# p3.net
KiCad netlist of a schematic drawn in EAGLE
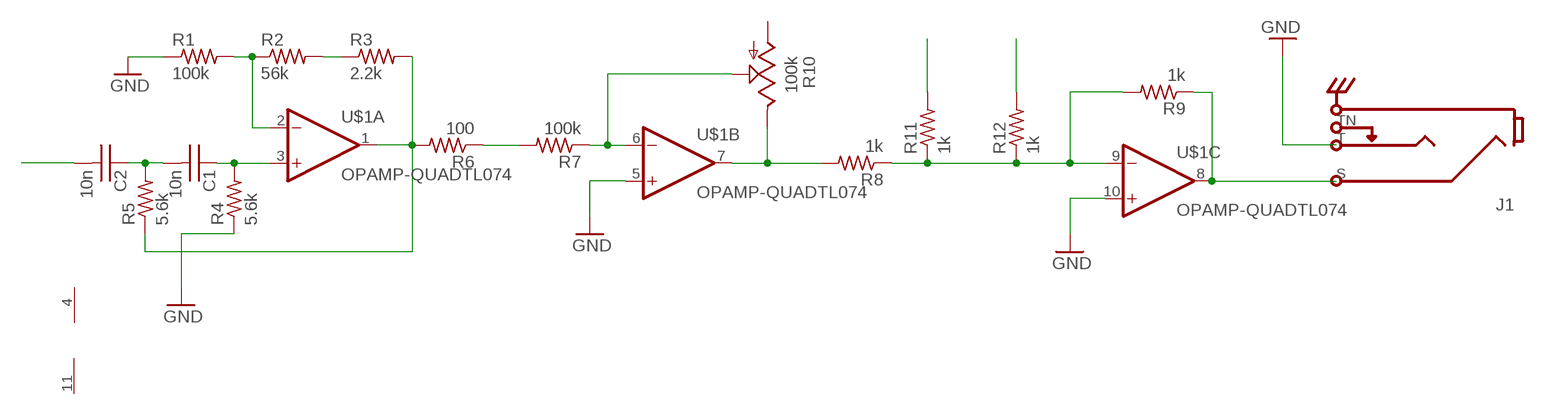
[diagram p0: schematic, sheet 1]

(export (version "E")
  (design (tool "Eeschema 10.0.6"))
  (components
    (comp (ref "C1")
      (value "10n")
      (footprint "eagle-import:BOX-2.5MM-7.2MM")
      (libsource (lib "eagle-import") (part "CAPACITOR"))
    )
    (comp (ref "C2")
      (value "10n")
      (footprint "eagle-import:BOX-2.5MM-7.2MM")
      (libsource (lib "eagle-import") (part "CAPACITOR"))
    )
    (comp (ref "J1")
      (value "MONOSW1GND")
      (footprint "eagle-import:NEUTRIK-NRJ4HM-1")
      (libsource (lib "eagle-import") (part "MONOSW1GND"))
    )
    (comp (ref "R1")
      (value "100k")
      (footprint "eagle-import:0.25W-0.4IN-METALFILM")
      (libsource (lib "eagle-import") (part "RESISTOR0.25W-0.4IN-METALFILM"))
    )
    (comp (ref "R2")
      (value "56k")
      (footprint "eagle-import:0.25W-0.4IN-METALFILM")
      (libsource (lib "eagle-import") (part "RESISTOR0.25W-0.4IN-METALFILM"))
    )
    (comp (ref "R3")
      (value "2.2k")
      (footprint "eagle-import:0.25W-0.4IN-METALFILM")
      (libsource (lib "eagle-import") (part "RESISTOR0.25W-0.4IN-METALFILM"))
    )
    (comp (ref "R4")
      (value "5.6k")
      (footprint "eagle-import:0.25W-0.4IN-METALFILM")
      (libsource (lib "eagle-import") (part "RESISTOR0.25W-0.4IN-METALFILM"))
    )
    (comp (ref "R5")
      (value "5.6k")
      (footprint "eagle-import:0.25W-0.4IN-METALFILM")
      (libsource (lib "eagle-import") (part "RESISTOR0.25W-0.4IN-METALFILM"))
    )
    (comp (ref "R6")
      (value "100")
      (footprint "eagle-import:0.25W-0.4IN-METALFILM")
      (libsource (lib "eagle-import") (part "RESISTOR0.25W-0.4IN-METALFILM"))
    )
    (comp (ref "R7")
      (value "100k")
      (footprint "eagle-import:0.25W-0.4IN-METALFILM")
      (libsource (lib "eagle-import") (part "RESISTOR0.25W-0.4IN-METALFILM"))
    )
    (comp (ref "R8")
      (value "1k")
      (footprint "eagle-import:0.25W-0.4IN-METALFILM")
      (libsource (lib "eagle-import") (part "RESISTOR0.25W-0.4IN-METALFILM"))
    )
    (comp (ref "R9")
      (value "1k")
      (footprint "eagle-import:0.25W-0.4IN-METALFILM")
      (libsource (lib "eagle-import") (part "RESISTOR0.25W-0.4IN-METALFILM"))
    )
    (comp (ref "R10")
      (value "100k")
      (footprint "eagle-import:POT-SIDE-16MM-BITECH-P160KN")
      (libsource (lib "eagle-import") (part "POTENTIOMETERHORIZONTAL"))
    )
    (comp (ref "R11")
      (value "1k")
      (footprint "eagle-import:0.25W-0.4IN")
      (libsource (lib "eagle-import") (part "RESISTOR0.25W-0.4IN"))
    )
    (comp (ref "R12")
      (value "1k")
      (footprint "eagle-import:0.25W-0.4IN")
      (libsource (lib "eagle-import") (part "RESISTOR0.25W-0.4IN"))
    )
    (comp (ref "U$1")
      (value "OPAMP-QUADTL074")
      (footprint "eagle-import:DIP14")
      (libsource (lib "eagle-import") (part "OPAMP-QUADTL074"))
    )
  )
  (nets
    (net (code "1") (name "/VCC") (class "Default")
      (node (ref "U$1") (pin "4") (pinfunction "VCC_4") (pintype "power_in"))
    )
    (net (code "2") (name "/VEE") (class "Default")
      (node (ref "U$1") (pin "11") (pinfunction "VEE_11") (pintype "power_in"))
    )
    (net (code "3") (name "0") (class "Default")
      (node (ref "J1") (pin "T") (pinfunction "T_T") (pintype "passive"))
      (node (ref "R1") (pin "1") (pinfunction "1_1") (pintype "passive"))
      (node (ref "R4") (pin "1") (pinfunction "1_1") (pintype "passive"))
      (node (ref "U$1") (pin "10") (pinfunction "IN+_10") (pintype "input"))
      (node (ref "U$1") (pin "5") (pinfunction "IN+_5") (pintype "input"))
    )
    (net (code "4") (name "Net-(C1-1)") (class "Default")
      (node (ref "C1") (pin "P$1") (pinfunction "1_P$1") (pintype "passive"))
      (node (ref "R4") (pin "2") (pinfunction "2_2") (pintype "passive"))
      (node (ref "U$1") (pin "3") (pinfunction "IN+_3") (pintype "input"))
    )
    (net (code "5") (name "Net-(C1-2)") (class "Default")
      (node (ref "C1") (pin "P$2") (pinfunction "2_P$2") (pintype "passive"))
      (node (ref "C2") (pin "P$1") (pinfunction "1_P$1") (pintype "passive"))
      (node (ref "R5") (pin "2") (pinfunction "2_2") (pintype "passive"))
    )
    (net (code "6") (name "Net-(R2-Pad2)") (class "Default")
      (node (ref "R2") (pin "2") (pinfunction "2_2") (pintype "passive"))
      (node (ref "R3") (pin "1") (pinfunction "1_1") (pintype "passive"))
    )
    (net (code "7") (name "Net-(R6-Pad1)") (class "Default")
      (node (ref "R6") (pin "1") (pinfunction "1_1") (pintype "passive"))
      (node (ref "R7") (pin "2") (pinfunction "2_2") (pintype "passive"))
    )
    (net (code "8") (name "Net-(R10-2)") (class "Default")
      (node (ref "R10") (pin "P$2") (pinfunction "2_P$2") (pintype "passive"))
      (node (ref "R7") (pin "1") (pinfunction "1_1") (pintype "passive"))
      (node (ref "U$1") (pin "6") (pinfunction "IN-_6") (pintype "input"))
    )
    (net (code "9") (name "Net-(R10-3)") (class "Default")
      (node (ref "R10") (pin "P$3") (pinfunction "3_P$3") (pintype "passive"))
      (node (ref "R8") (pin "2") (pinfunction "2_2") (pintype "passive"))
      (node (ref "U$1") (pin "7") (pinfunction "OUT_7") (pintype "output"))
    )
    (net (code "10") (name "Net-(U$1A-IN-)") (class "Default")
      (node (ref "R1") (pin "2") (pinfunction "2_2") (pintype "passive"))
      (node (ref "R2") (pin "1") (pinfunction "1_1") (pintype "passive"))
      (node (ref "U$1") (pin "2") (pinfunction "IN-_2") (pintype "input"))
    )
    (net (code "11") (name "Net-(U$1A-OUT)") (class "Default")
      (node (ref "R3") (pin "2") (pinfunction "2_2") (pintype "passive"))
      (node (ref "R5") (pin "1") (pinfunction "1_1") (pintype "passive"))
      (node (ref "R6") (pin "2") (pinfunction "2_2") (pintype "passive"))
      (node (ref "U$1") (pin "1") (pinfunction "OUT_1") (pintype "output"))
    )
    (net (code "12") (name "Net-(U$1C-IN-)") (class "Default")
      (node (ref "R11") (pin "1") (pinfunction "1_1") (pintype "passive"))
      (node (ref "R12") (pin "1") (pinfunction "1_1") (pintype "passive"))
      (node (ref "R8") (pin "1") (pinfunction "1_1") (pintype "passive"))
      (node (ref "R9") (pin "2") (pinfunction "2_2") (pintype "passive"))
      (node (ref "U$1") (pin "9") (pinfunction "IN-_9") (pintype "input"))
    )
    (net (code "13") (name "Net-(U$1C-OUT)") (class "Default")
      (node (ref "J1") (pin "S") (pinfunction "S_S") (pintype "passive"))
      (node (ref "R9") (pin "1") (pinfunction "1_1") (pintype "passive"))
      (node (ref "U$1") (pin "8") (pinfunction "OUT_8") (pintype "output"))
    )
    (net (code "14") (name "unconnected-(C2-2-PadP$2)") (class "Default")
      (node (ref "C2") (pin "P$2") (pinfunction "2_P$2") (pintype "passive"))
    )
    (net (code "15") (name "unconnected-(J1-PadTN)") (class "Default")
      (node (ref "J1") (pin "TN") (pinfunction "TN_TN") (pintype "passive"))
    )
    (net (code "16") (name "unconnected-(R10-1-PadP$1)") (class "Default")
      (node (ref "R10") (pin "P$1") (pinfunction "1_P$1") (pintype "passive"))
    )
    (net (code "17") (name "unconnected-(R11-Pad2)") (class "Default")
      (node (ref "R11") (pin "2") (pinfunction "2_2") (pintype "passive"))
    )
    (net (code "18") (name "unconnected-(R12-Pad2)") (class "Default")
      (node (ref "R12") (pin "2") (pinfunction "2_2") (pintype "passive"))
    )
  )
)
